# ESP-XBee.net
KiCad netlist of a schematic drawn in EAGLE
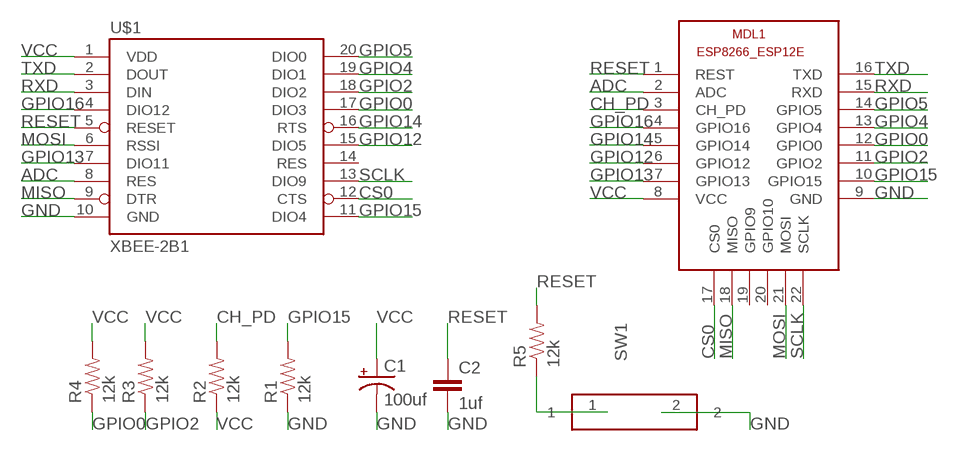
[diagram p0: schematic, sheet 1]

(export (version "E")
  (design (tool "Eeschema 10.0.6"))
  (components
    (comp (ref "C1")
      (value "100uf")
      (footprint "eagle-import:EIA3216-KIT")
      (libsource (lib "eagle-import") (part "CAP_POL1206-KIT"))
    )
    (comp (ref "C2")
      (value "1uf")
      (footprint "eagle-import:0805")
      (libsource (lib "eagle-import") (part "CAP0805"))
    )
    (comp (ref "MDL1")
      (value "ESP8266-12EESP8266-ESP12E")
      (footprint "eagle-import:ESP8266-ESP12E")
      (libsource (lib "eagle-import") (part "ESP8266-12EESP8266-ESP12E"))
    )
    (comp (ref "R1")
      (value "12k")
      (footprint "eagle-import:0805")
      (libsource (lib "eagle-import") (part "RESISTOR0805-RES"))
    )
    (comp (ref "R2")
      (value "12k")
      (footprint "eagle-import:0805")
      (libsource (lib "eagle-import") (part "RESISTOR0805-RES"))
    )
    (comp (ref "R3")
      (value "12k")
      (footprint "eagle-import:0805")
      (libsource (lib "eagle-import") (part "RESISTOR0805-RES"))
    )
    (comp (ref "R4")
      (value "12k")
      (footprint "eagle-import:0805")
      (libsource (lib "eagle-import") (part "RESISTOR0805-RES"))
    )
    (comp (ref "R5")
      (value "12k")
      (footprint "eagle-import:0805")
      (libsource (lib "eagle-import") (part "RESISTOR0805-RES"))
    )
    (comp (ref "SW1")
      (value "434111043826")
      (footprint "eagle-import:434111043826")
      (libsource (lib "eagle-import") (part "434111043826"))
    )
    (comp (ref "U$1")
      (value "XBEE-2B1")
      (footprint "eagle-import:XBEE-1")
      (libsource (lib "eagle-import") (part "XBEE-2B1"))
    )
  )
  (nets
    (net (code "1") (name "/ADC") (class "Default")
      (node (ref "MDL1") (pin "2") (pinfunction "ADC_2") (pintype "bidirectional"))
      (node (ref "U$1") (pin "8") (pinfunction "RES_8") (pintype "bidirectional"))
    )
    (net (code "2") (name "/CH_PD") (class "Default")
      (node (ref "MDL1") (pin "3") (pinfunction "CH_PD_3") (pintype "bidirectional"))
      (node (ref "R2") (pin "2") (pinfunction "2_2") (pintype "passive"))
    )
    (net (code "3") (name "/CS0") (class "Default")
      (node (ref "MDL1") (pin "17") (pinfunction "CS0_17") (pintype "bidirectional"))
      (node (ref "U$1") (pin "12") (pinfunction "CTS_12") (pintype "output"))
    )
    (net (code "4") (name "/GND") (class "Default")
      (node (ref "C1") (pin "C") (pinfunction "-_C") (pintype "passive"))
      (node (ref "C2") (pin "2") (pinfunction "2_2") (pintype "passive"))
      (node (ref "MDL1") (pin "9") (pinfunction "GND_9") (pintype "bidirectional"))
      (node (ref "R1") (pin "1") (pinfunction "1_1") (pintype "passive"))
      (node (ref "SW1") (pin "2") (pinfunction "2_2") (pintype "bidirectional"))
      (node (ref "U$1") (pin "10") (pinfunction "GND_10") (pintype "power_in"))
    )
    (net (code "5") (name "/GPIO0") (class "Default")
      (node (ref "MDL1") (pin "12") (pinfunction "GPIO0_12") (pintype "bidirectional"))
      (node (ref "R4") (pin "1") (pinfunction "1_1") (pintype "passive"))
      (node (ref "U$1") (pin "17") (pinfunction "DIO3_17") (pintype "bidirectional"))
    )
    (net (code "6") (name "/GPIO2") (class "Default")
      (node (ref "MDL1") (pin "11") (pinfunction "GPIO2_11") (pintype "bidirectional"))
      (node (ref "R3") (pin "1") (pinfunction "1_1") (pintype "passive"))
      (node (ref "U$1") (pin "18") (pinfunction "DIO2_18") (pintype "bidirectional"))
    )
    (net (code "7") (name "/GPIO4") (class "Default")
      (node (ref "MDL1") (pin "13") (pinfunction "GPIO4_13") (pintype "bidirectional"))
      (node (ref "U$1") (pin "19") (pinfunction "DIO1_19") (pintype "bidirectional"))
    )
    (net (code "8") (name "/GPIO5") (class "Default")
      (node (ref "MDL1") (pin "14") (pinfunction "GPIO5_14") (pintype "bidirectional"))
      (node (ref "U$1") (pin "20") (pinfunction "DIO0_20") (pintype "bidirectional"))
    )
    (net (code "9") (name "/GPIO12") (class "Default")
      (node (ref "MDL1") (pin "6") (pinfunction "GPIO12_6") (pintype "bidirectional"))
      (node (ref "U$1") (pin "15") (pinfunction "DIO5_15") (pintype "bidirectional"))
    )
    (net (code "10") (name "/GPIO13") (class "Default")
      (node (ref "MDL1") (pin "7") (pinfunction "GPIO13_7") (pintype "bidirectional"))
      (node (ref "U$1") (pin "7") (pinfunction "DIO11_7") (pintype "bidirectional"))
    )
    (net (code "11") (name "/GPIO14") (class "Default")
      (node (ref "MDL1") (pin "5") (pinfunction "GPIO14_5") (pintype "bidirectional"))
      (node (ref "U$1") (pin "16") (pinfunction "RTS_16") (pintype "input"))
    )
    (net (code "12") (name "/GPIO15") (class "Default")
      (node (ref "MDL1") (pin "10") (pinfunction "GPIO15_10") (pintype "bidirectional"))
      (node (ref "R1") (pin "2") (pinfunction "2_2") (pintype "passive"))
      (node (ref "U$1") (pin "11") (pinfunction "DIO4_11") (pintype "bidirectional"))
    )
    (net (code "13") (name "/GPIO16") (class "Default")
      (node (ref "MDL1") (pin "4") (pinfunction "GPIO16_4") (pintype "bidirectional"))
      (node (ref "U$1") (pin "4") (pinfunction "DIO12_4") (pintype "bidirectional"))
    )
    (net (code "14") (name "/MISO") (class "Default")
      (node (ref "MDL1") (pin "18") (pinfunction "MISO_18") (pintype "bidirectional"))
      (node (ref "U$1") (pin "9") (pinfunction "DTR_9") (pintype "bidirectional"))
    )
    (net (code "15") (name "/MOSI") (class "Default")
      (node (ref "MDL1") (pin "21") (pinfunction "MOSI_21") (pintype "bidirectional"))
      (node (ref "U$1") (pin "6") (pinfunction "RSSI_6") (pintype "bidirectional"))
    )
    (net (code "16") (name "/RESET") (class "Default")
      (node (ref "C2") (pin "1") (pinfunction "1_1") (pintype "passive"))
      (node (ref "MDL1") (pin "1") (pinfunction "REST_1") (pintype "bidirectional"))
      (node (ref "R5") (pin "2") (pinfunction "2_2") (pintype "passive"))
      (node (ref "U$1") (pin "5") (pinfunction "RESET_5") (pintype "input"))
    )
    (net (code "17") (name "/RXD") (class "Default")
      (node (ref "MDL1") (pin "15") (pinfunction "RXD_15") (pintype "bidirectional"))
      (node (ref "U$1") (pin "3") (pinfunction "DIN_3") (pintype "input"))
    )
    (net (code "18") (name "/SCLK") (class "Default")
      (node (ref "MDL1") (pin "22") (pinfunction "SCLK_22") (pintype "bidirectional"))
      (node (ref "U$1") (pin "13") (pinfunction "DIO9_13") (pintype "bidirectional"))
    )
    (net (code "19") (name "/TXD") (class "Default")
      (node (ref "MDL1") (pin "16") (pinfunction "TXD_16") (pintype "bidirectional"))
      (node (ref "U$1") (pin "2") (pinfunction "DOUT_2") (pintype "output"))
    )
    (net (code "20") (name "/VCC") (class "Default")
      (node (ref "C1") (pin "A") (pinfunction "+_A") (pintype "passive"))
      (node (ref "MDL1") (pin "8") (pinfunction "VCC_8") (pintype "bidirectional"))
      (node (ref "R2") (pin "1") (pinfunction "1_1") (pintype "passive"))
      (node (ref "R3") (pin "2") (pinfunction "2_2") (pintype "passive"))
      (node (ref "R4") (pin "2") (pinfunction "2_2") (pintype "passive"))
      (node (ref "U$1") (pin "1") (pinfunction "VDD_1") (pintype "power_in"))
    )
    (net (code "21") (name "Net-(R5-Pad1)") (class "Default")
      (node (ref "R5") (pin "1") (pinfunction "1_1") (pintype "passive"))
      (node (ref "SW1") (pin "1") (pinfunction "1_1") (pintype "bidirectional"))
    )
    (net (code "22") (name "unconnected-(MDL1-GPIO9-Pad19)") (class "Default")
      (node (ref "MDL1") (pin "19") (pinfunction "GPIO9_19") (pintype "bidirectional"))
    )
    (net (code "23") (name "unconnected-(MDL1-GPIO10-Pad20)") (class "Default")
      (node (ref "MDL1") (pin "20") (pinfunction "GPIO10_20") (pintype "bidirectional"))
    )
    (net (code "24") (name "unconnected-(U$1-RES-Pad14)") (class "Default")
      (node (ref "U$1") (pin "14") (pinfunction "RES_14") (pintype "bidirectional"))
    )
  )
)
